# Sensor_PCB.net
KiCad netlist of a schematic drawn in Altium Designer
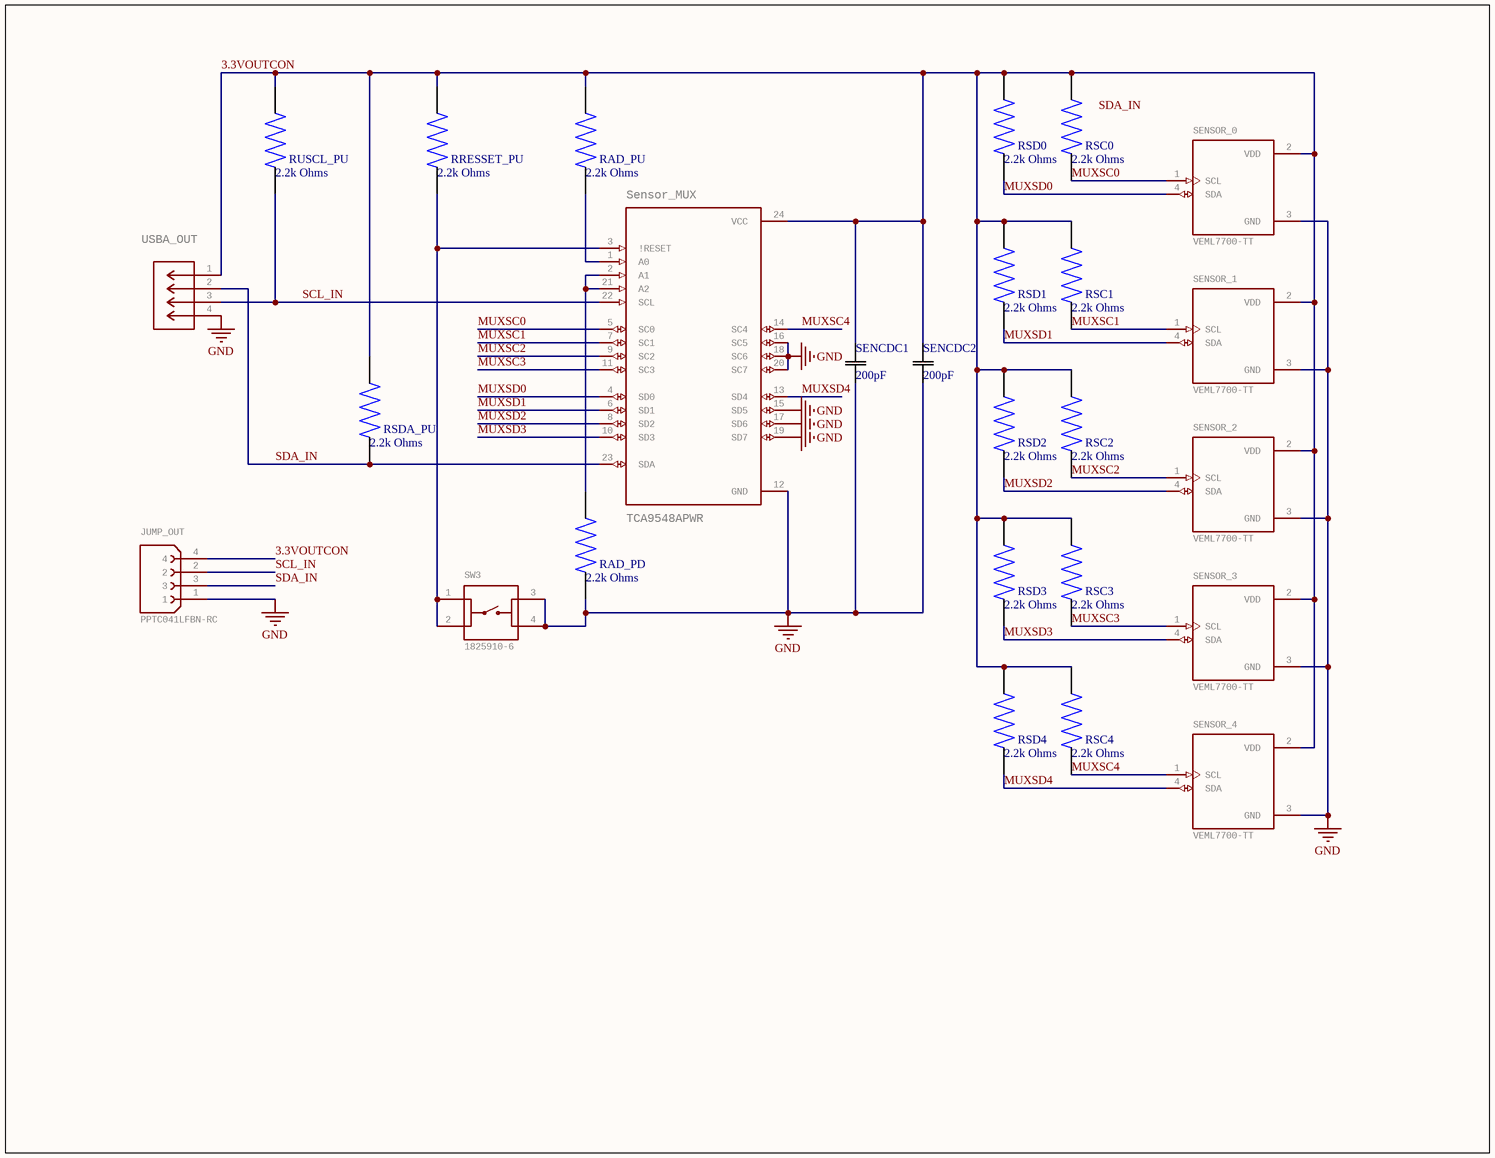
[diagram p0: Sensor_PCB.SchDoc]

(export (version "E")
  (design (tool "Eeschema 10.0.6"))
  (components
    (comp (ref "JUMP_OUT")
      (value "PPTC041LFBN-RC")
      (footprint "SULLINS_PPTC041LFBN-RC")
      (description "4 Position Header Connector Through Hole  Check availability")
      (fields (field (name "MF") "Sullins Connector"))
      (libsource (lib "PPTC041LFBN-RC") (part "PPTC041LFBN-RC"))
    )
    (comp (ref "RAD_PD")
      (value "2.2k Ohms")
      (footprint "AC0805FR-072K2L:RESC2012X60N")
      (description "RES SMD 2.2K OHM 1% 1/8W 0805")
      (fields (field (name "MP") "AC0805FR-072K2L"))
      (libsource (lib "AC0805FR-072K2L") (part "AC0805FR-072K2L"))
    )
    (comp (ref "RAD_PU")
      (value "2.2k Ohms")
      (footprint "AC0805FR-072K2L:RESC2012X60N")
      (description "RES SMD 2.2K OHM 1% 1/8W 0805")
      (fields (field (name "MP") "AC0805FR-072K2L"))
      (libsource (lib "AC0805FR-072K2L") (part "AC0805FR-072K2L"))
    )
    (comp (ref "RRESSET_PU")
      (value "2.2k Ohms")
      (footprint "AC0805FR-072K2L:RESC2012X60N")
      (description "RES SMD 2.2K OHM 1% 1/8W 0805")
      (fields (field (name "MP") "AC0805FR-072K2L"))
      (libsource (lib "AC0805FR-072K2L") (part "AC0805FR-072K2L"))
    )
    (comp (ref "RSC0")
      (value "2.2k Ohms")
      (footprint "AC0805FR-072K2L:RESC2012X60N")
      (description "RES SMD 2.2K OHM 1% 1/8W 0805")
      (fields (field (name "MP") "AC0805FR-072K2L"))
      (libsource (lib "AC0805FR-072K2L") (part "AC0805FR-072K2L"))
    )
    (comp (ref "RSC1")
      (value "2.2k Ohms")
      (footprint "AC0805FR-072K2L:RESC2012X60N")
      (description "RES SMD 2.2K OHM 1% 1/8W 0805")
      (fields (field (name "MP") "AC0805FR-072K2L"))
      (libsource (lib "AC0805FR-072K2L") (part "AC0805FR-072K2L"))
    )
    (comp (ref "RSC2")
      (value "2.2k Ohms")
      (footprint "AC0805FR-072K2L:RESC2012X60N")
      (description "RES SMD 2.2K OHM 1% 1/8W 0805")
      (fields (field (name "MP") "AC0805FR-072K2L"))
      (libsource (lib "AC0805FR-072K2L") (part "AC0805FR-072K2L"))
    )
    (comp (ref "RSC3")
      (value "2.2k Ohms")
      (footprint "AC0805FR-072K2L:RESC2012X60N")
      (description "RES SMD 2.2K OHM 1% 1/8W 0805")
      (fields (field (name "MP") "AC0805FR-072K2L"))
      (libsource (lib "AC0805FR-072K2L") (part "AC0805FR-072K2L"))
    )
    (comp (ref "RSC4")
      (value "2.2k Ohms")
      (footprint "AC0805FR-072K2L:RESC2012X60N")
      (description "RES SMD 2.2K OHM 1% 1/8W 0805")
      (fields (field (name "MP") "AC0805FR-072K2L"))
      (libsource (lib "AC0805FR-072K2L") (part "AC0805FR-072K2L"))
    )
    (comp (ref "RSD0")
      (value "2.2k Ohms")
      (footprint "AC0805FR-072K2L:RESC2012X60N")
      (description "RES SMD 2.2K OHM 1% 1/8W 0805")
      (fields (field (name "MP") "AC0805FR-072K2L"))
      (libsource (lib "AC0805FR-072K2L") (part "AC0805FR-072K2L"))
    )
    (comp (ref "RSD1")
      (value "2.2k Ohms")
      (footprint "AC0805FR-072K2L:RESC2012X60N")
      (description "RES SMD 2.2K OHM 1% 1/8W 0805")
      (fields (field (name "MP") "AC0805FR-072K2L"))
      (libsource (lib "AC0805FR-072K2L") (part "AC0805FR-072K2L"))
    )
    (comp (ref "RSD2")
      (value "2.2k Ohms")
      (footprint "AC0805FR-072K2L:RESC2012X60N")
      (description "RES SMD 2.2K OHM 1% 1/8W 0805")
      (fields (field (name "MP") "AC0805FR-072K2L"))
      (libsource (lib "AC0805FR-072K2L") (part "AC0805FR-072K2L"))
    )
    (comp (ref "RSD3")
      (value "2.2k Ohms")
      (footprint "AC0805FR-072K2L:RESC2012X60N")
      (description "RES SMD 2.2K OHM 1% 1/8W 0805")
      (fields (field (name "MP") "AC0805FR-072K2L"))
      (libsource (lib "AC0805FR-072K2L") (part "AC0805FR-072K2L"))
    )
    (comp (ref "RSD4")
      (value "2.2k Ohms")
      (footprint "AC0805FR-072K2L:RESC2012X60N")
      (description "RES SMD 2.2K OHM 1% 1/8W 0805")
      (fields (field (name "MP") "AC0805FR-072K2L"))
      (libsource (lib "AC0805FR-072K2L") (part "AC0805FR-072K2L"))
    )
    (comp (ref "RSDA_PU")
      (value "2.2k Ohms")
      (footprint "AC0805FR-072K2L:RESC2012X60N")
      (description "RES SMD 2.2K OHM 1% 1/8W 0805")
      (fields (field (name "MP") "AC0805FR-072K2L"))
      (libsource (lib "AC0805FR-072K2L") (part "AC0805FR-072K2L"))
    )
    (comp (ref "RUSCL_PU")
      (value "2.2k Ohms")
      (footprint "AC0805FR-072K2L:RESC2012X60N")
      (description "RES SMD 2.2K OHM 1% 1/8W 0805")
      (fields (field (name "MP") "AC0805FR-072K2L"))
      (libsource (lib "AC0805FR-072K2L") (part "AC0805FR-072K2L"))
    )
    (comp (ref "SENCDC1")
      (value "200pF")
      (footprint "CAP_CC0805_YAG")
      (description "CAP CER 200PF 50V X7R 0805")
      (fields
        (field (name "MANUFACTURER_PART_NUMBER") "CC0805KRX7R9BB201")
        (field (name "COPYRIGHT") "Copyright (C) 2023 Ultra Librarian. All rights reserved.")
      )
      (libsource (lib "CC0805KRX7R9BB201") (part "CC0805KRX7R9BB201"))
    )
    (comp (ref "SENCDC2")
      (value "200pF")
      (footprint "CAP_CC0805_YAG")
      (description "CAP CER 200PF 50V X7R 0805")
      (fields
        (field (name "MANUFACTURER_PART_NUMBER") "CC0805KRX7R9BB201")
        (field (name "COPYRIGHT") "Copyright (C) 2023 Ultra Librarian. All rights reserved.")
      )
      (libsource (lib "CC0805KRX7R9BB201") (part "CC0805KRX7R9BB201"))
    )
    (comp (ref "SENSOR_0")
      (value "VEML7700-TT")
      (footprint "XDCR_VEML7700-TT")
      (fields (field (name "MF") "Vishay Semiconductor"))
      (libsource (lib "VEML7700-TT") (part "VEML7700-TT"))
    )
    (comp (ref "SENSOR_1")
      (value "VEML7700-TT")
      (footprint "XDCR_VEML7700-TT")
      (fields (field (name "MF") "Vishay Semiconductor"))
      (libsource (lib "VEML7700-TT") (part "VEML7700-TT"))
    )
    (comp (ref "SENSOR_2")
      (value "VEML7700-TT")
      (footprint "XDCR_VEML7700-TT")
      (fields (field (name "MF") "Vishay Semiconductor"))
      (libsource (lib "VEML7700-TT") (part "VEML7700-TT"))
    )
    (comp (ref "SENSOR_3")
      (value "VEML7700-TT")
      (footprint "XDCR_VEML7700-TT")
      (fields (field (name "MF") "Vishay Semiconductor"))
      (libsource (lib "VEML7700-TT") (part "VEML7700-TT"))
    )
    (comp (ref "SENSOR_4")
      (value "VEML7700-TT")
      (footprint "XDCR_VEML7700-TT")
      (fields (field (name "MF") "Vishay Semiconductor"))
      (libsource (lib "VEML7700-TT") (part "VEML7700-TT"))
    )
    (comp (ref "Sensor_MUX")
      (value "TCA9548APWR")
      (footprint "SOP65P640X120-24N")
      (description "IC BUS SWITCH 1 X 8:1 24TSSOP")
      (fields (field (name "MF") "Texas Instruments"))
      (libsource (lib "TCA9548APWR") (part "TCA9548APWR"))
    )
    (comp (ref "SW3")
      (value "1825910-6")
      (footprint "SW_1825910-6-4")
      (description "SWITCH TACTILE SPST-NO 0.05A 24V")
      (fields (field (name "MF") "TE Connectivity"))
      (libsource (lib "1825910-6") (part "1825910-6"))
    )
    (comp (ref "USBA_OUT")
      (value "USB-AP-S-RA-SMT")
      (footprint "CONN_USB-AP-S-RA-SMT_ADM")
      (description "USB A 2.0, R/A, SMT, PLUG")
      (fields (field (name "COPYRIGHT") "Copyright (C) 2023 Ultra Librarian. All rights reserved."))
      (libsource (lib "USB-AP-S-RA-SMT") (part "USB-AP-S-RA-SMT"))
    )
  )
  (nets
    (net (code "1") (name "/3.3VOUTCON") (class "Default")
      (node (ref "JUMP_OUT") (pin "4") (pinfunction "4_4") (pintype "passive"))
      (node (ref "RAD_PU") (pin "2") (pinfunction "2_2") (pintype "passive"))
      (node (ref "RRESSET_PU") (pin "2") (pinfunction "2_2") (pintype "passive"))
      (node (ref "RSC0") (pin "2") (pinfunction "2_2") (pintype "passive"))
      (node (ref "RSC1") (pin "2") (pinfunction "2_2") (pintype "passive"))
      (node (ref "RSC2") (pin "2") (pinfunction "2_2") (pintype "passive"))
      (node (ref "RSC3") (pin "2") (pinfunction "2_2") (pintype "passive"))
      (node (ref "RSC4") (pin "2") (pinfunction "2_2") (pintype "passive"))
      (node (ref "RSD0") (pin "2") (pinfunction "2_2") (pintype "passive"))
      (node (ref "RSD1") (pin "2") (pinfunction "2_2") (pintype "passive"))
      (node (ref "RSD2") (pin "2") (pinfunction "2_2") (pintype "passive"))
      (node (ref "RSD3") (pin "2") (pinfunction "2_2") (pintype "passive"))
      (node (ref "RSD4") (pin "2") (pinfunction "2_2") (pintype "passive"))
      (node (ref "RSDA_PU") (pin "2") (pinfunction "2_2") (pintype "passive"))
      (node (ref "RUSCL_PU") (pin "2") (pinfunction "2_2") (pintype "passive"))
      (node (ref "SENCDC1") (pin "2") (pinfunction "2_2") (pintype "passive"))
      (node (ref "SENCDC2") (pin "2") (pinfunction "2_2") (pintype "passive"))
      (node (ref "SENSOR_0") (pin "2") (pinfunction "VDD_2") (pintype "power_in"))
      (node (ref "SENSOR_1") (pin "2") (pinfunction "VDD_2") (pintype "power_in"))
      (node (ref "SENSOR_2") (pin "2") (pinfunction "VDD_2") (pintype "power_in"))
      (node (ref "SENSOR_3") (pin "2") (pinfunction "VDD_2") (pintype "power_in"))
      (node (ref "SENSOR_4") (pin "2") (pinfunction "VDD_2") (pintype "power_in"))
      (node (ref "Sensor_MUX") (pin "24") (pinfunction "VCC_24") (pintype "power_in"))
      (node (ref "USBA_OUT") (pin "1") (pinfunction "1_1") (pintype "passive"))
    )
    (net (code "2") (name "/MUXSC0") (class "Default")
      (node (ref "RSC0") (pin "1") (pinfunction "1_1") (pintype "passive"))
      (node (ref "SENSOR_0") (pin "1") (pinfunction "SCL_1") (pintype "input"))
      (node (ref "Sensor_MUX") (pin "5") (pinfunction "SC0_5") (pintype "bidirectional"))
    )
    (net (code "3") (name "/MUXSC1") (class "Default")
      (node (ref "RSC1") (pin "1") (pinfunction "1_1") (pintype "passive"))
      (node (ref "SENSOR_1") (pin "1") (pinfunction "SCL_1") (pintype "input"))
      (node (ref "Sensor_MUX") (pin "7") (pinfunction "SC1_7") (pintype "bidirectional"))
    )
    (net (code "4") (name "/MUXSC2") (class "Default")
      (node (ref "RSC2") (pin "1") (pinfunction "1_1") (pintype "passive"))
      (node (ref "SENSOR_2") (pin "1") (pinfunction "SCL_1") (pintype "input"))
      (node (ref "Sensor_MUX") (pin "9") (pinfunction "SC2_9") (pintype "bidirectional"))
    )
    (net (code "5") (name "/MUXSC3") (class "Default")
      (node (ref "RSC3") (pin "1") (pinfunction "1_1") (pintype "passive"))
      (node (ref "SENSOR_3") (pin "1") (pinfunction "SCL_1") (pintype "input"))
      (node (ref "Sensor_MUX") (pin "11") (pinfunction "SC3_11") (pintype "bidirectional"))
    )
    (net (code "6") (name "/MUXSC4") (class "Default")
      (node (ref "RSC4") (pin "1") (pinfunction "1_1") (pintype "passive"))
      (node (ref "SENSOR_4") (pin "1") (pinfunction "SCL_1") (pintype "input"))
      (node (ref "Sensor_MUX") (pin "14") (pinfunction "SC4_14") (pintype "bidirectional"))
    )
    (net (code "7") (name "/MUXSD0") (class "Default")
      (node (ref "RSD0") (pin "1") (pinfunction "1_1") (pintype "passive"))
      (node (ref "SENSOR_0") (pin "4") (pinfunction "SDA_4") (pintype "bidirectional"))
      (node (ref "Sensor_MUX") (pin "4") (pinfunction "SD0_4") (pintype "bidirectional"))
    )
    (net (code "8") (name "/MUXSD1") (class "Default")
      (node (ref "RSD1") (pin "1") (pinfunction "1_1") (pintype "passive"))
      (node (ref "SENSOR_1") (pin "4") (pinfunction "SDA_4") (pintype "bidirectional"))
      (node (ref "Sensor_MUX") (pin "6") (pinfunction "SD1_6") (pintype "bidirectional"))
    )
    (net (code "9") (name "/MUXSD2") (class "Default")
      (node (ref "RSD2") (pin "1") (pinfunction "1_1") (pintype "passive"))
      (node (ref "SENSOR_2") (pin "4") (pinfunction "SDA_4") (pintype "bidirectional"))
      (node (ref "Sensor_MUX") (pin "8") (pinfunction "SD2_8") (pintype "bidirectional"))
    )
    (net (code "10") (name "/MUXSD3") (class "Default")
      (node (ref "RSD3") (pin "1") (pinfunction "1_1") (pintype "passive"))
      (node (ref "SENSOR_3") (pin "4") (pinfunction "SDA_4") (pintype "bidirectional"))
      (node (ref "Sensor_MUX") (pin "10") (pinfunction "SD3_10") (pintype "bidirectional"))
    )
    (net (code "11") (name "/MUXSD4") (class "Default")
      (node (ref "RSD4") (pin "1") (pinfunction "1_1") (pintype "passive"))
      (node (ref "SENSOR_4") (pin "4") (pinfunction "SDA_4") (pintype "bidirectional"))
      (node (ref "Sensor_MUX") (pin "13") (pinfunction "SD4_13") (pintype "bidirectional"))
    )
    (net (code "12") (name "/SCL_IN") (class "Default")
      (node (ref "JUMP_OUT") (pin "2") (pinfunction "2_2") (pintype "passive"))
      (node (ref "RUSCL_PU") (pin "1") (pinfunction "1_1") (pintype "passive"))
      (node (ref "Sensor_MUX") (pin "22") (pinfunction "SCL_22") (pintype "input"))
      (node (ref "USBA_OUT") (pin "3") (pinfunction "3_3") (pintype "passive"))
    )
    (net (code "13") (name "/SDA_IN") (class "Default")
      (node (ref "JUMP_OUT") (pin "3") (pinfunction "3_3") (pintype "passive"))
      (node (ref "RSDA_PU") (pin "1") (pinfunction "1_1") (pintype "passive"))
      (node (ref "Sensor_MUX") (pin "23") (pinfunction "SDA_23") (pintype "bidirectional"))
      (node (ref "USBA_OUT") (pin "2") (pinfunction "2_2") (pintype "passive"))
    )
    (net (code "14") (name "GND") (class "Default")
      (node (ref "JUMP_OUT") (pin "1") (pinfunction "1_1") (pintype "passive"))
      (node (ref "RAD_PD") (pin "1") (pinfunction "1_1") (pintype "passive"))
      (node (ref "SENCDC1") (pin "1") (pinfunction "1_1") (pintype "passive"))
      (node (ref "SENCDC2") (pin "1") (pinfunction "1_1") (pintype "passive"))
      (node (ref "SENSOR_0") (pin "3") (pinfunction "GND_3") (pintype "power_in"))
      (node (ref "SENSOR_1") (pin "3") (pinfunction "GND_3") (pintype "power_in"))
      (node (ref "SENSOR_2") (pin "3") (pinfunction "GND_3") (pintype "power_in"))
      (node (ref "SENSOR_3") (pin "3") (pinfunction "GND_3") (pintype "power_in"))
      (node (ref "SENSOR_4") (pin "3") (pinfunction "GND_3") (pintype "power_in"))
      (node (ref "SW3") (pin "3") (pinfunction "3_3") (pintype "passive"))
      (node (ref "SW3") (pin "4") (pinfunction "4_4") (pintype "passive"))
      (node (ref "Sensor_MUX") (pin "12") (pinfunction "GND_12") (pintype "power_in"))
      (node (ref "Sensor_MUX") (pin "15") (pinfunction "SD5_15") (pintype "bidirectional"))
      (node (ref "Sensor_MUX") (pin "16") (pinfunction "SC5_16") (pintype "bidirectional"))
      (node (ref "Sensor_MUX") (pin "17") (pinfunction "SD6_17") (pintype "bidirectional"))
      (node (ref "Sensor_MUX") (pin "18") (pinfunction "SC6_18") (pintype "bidirectional"))
      (node (ref "Sensor_MUX") (pin "19") (pinfunction "SD7_19") (pintype "bidirectional"))
      (node (ref "Sensor_MUX") (pin "20") (pinfunction "SC7_20") (pintype "bidirectional"))
      (node (ref "USBA_OUT") (pin "4") (pinfunction "4_4") (pintype "passive"))
    )
    (net (code "15") (name "Net-(Sensor_MUX-!RESET)") (class "Default")
      (node (ref "RRESSET_PU") (pin "1") (pinfunction "1_1") (pintype "passive"))
      (node (ref "SW3") (pin "1") (pinfunction "1_1") (pintype "passive"))
      (node (ref "SW3") (pin "2") (pinfunction "2_2") (pintype "passive"))
      (node (ref "Sensor_MUX") (pin "3") (pinfunction "!RESET_3") (pintype "input"))
    )
    (net (code "16") (name "Net-(Sensor_MUX-A0)") (class "Default")
      (node (ref "RAD_PU") (pin "1") (pinfunction "1_1") (pintype "passive"))
      (node (ref "Sensor_MUX") (pin "1") (pinfunction "A0_1") (pintype "input"))
    )
    (net (code "17") (name "Net-(Sensor_MUX-A1)") (class "Default")
      (node (ref "RAD_PD") (pin "2") (pinfunction "2_2") (pintype "passive"))
      (node (ref "Sensor_MUX") (pin "2") (pinfunction "A1_2") (pintype "input"))
      (node (ref "Sensor_MUX") (pin "21") (pinfunction "A2_21") (pintype "input"))
    )
  )
)
